# AD5764-AD7734_Synchronized.net
KiCad netlist of a schematic drawn in EAGLE
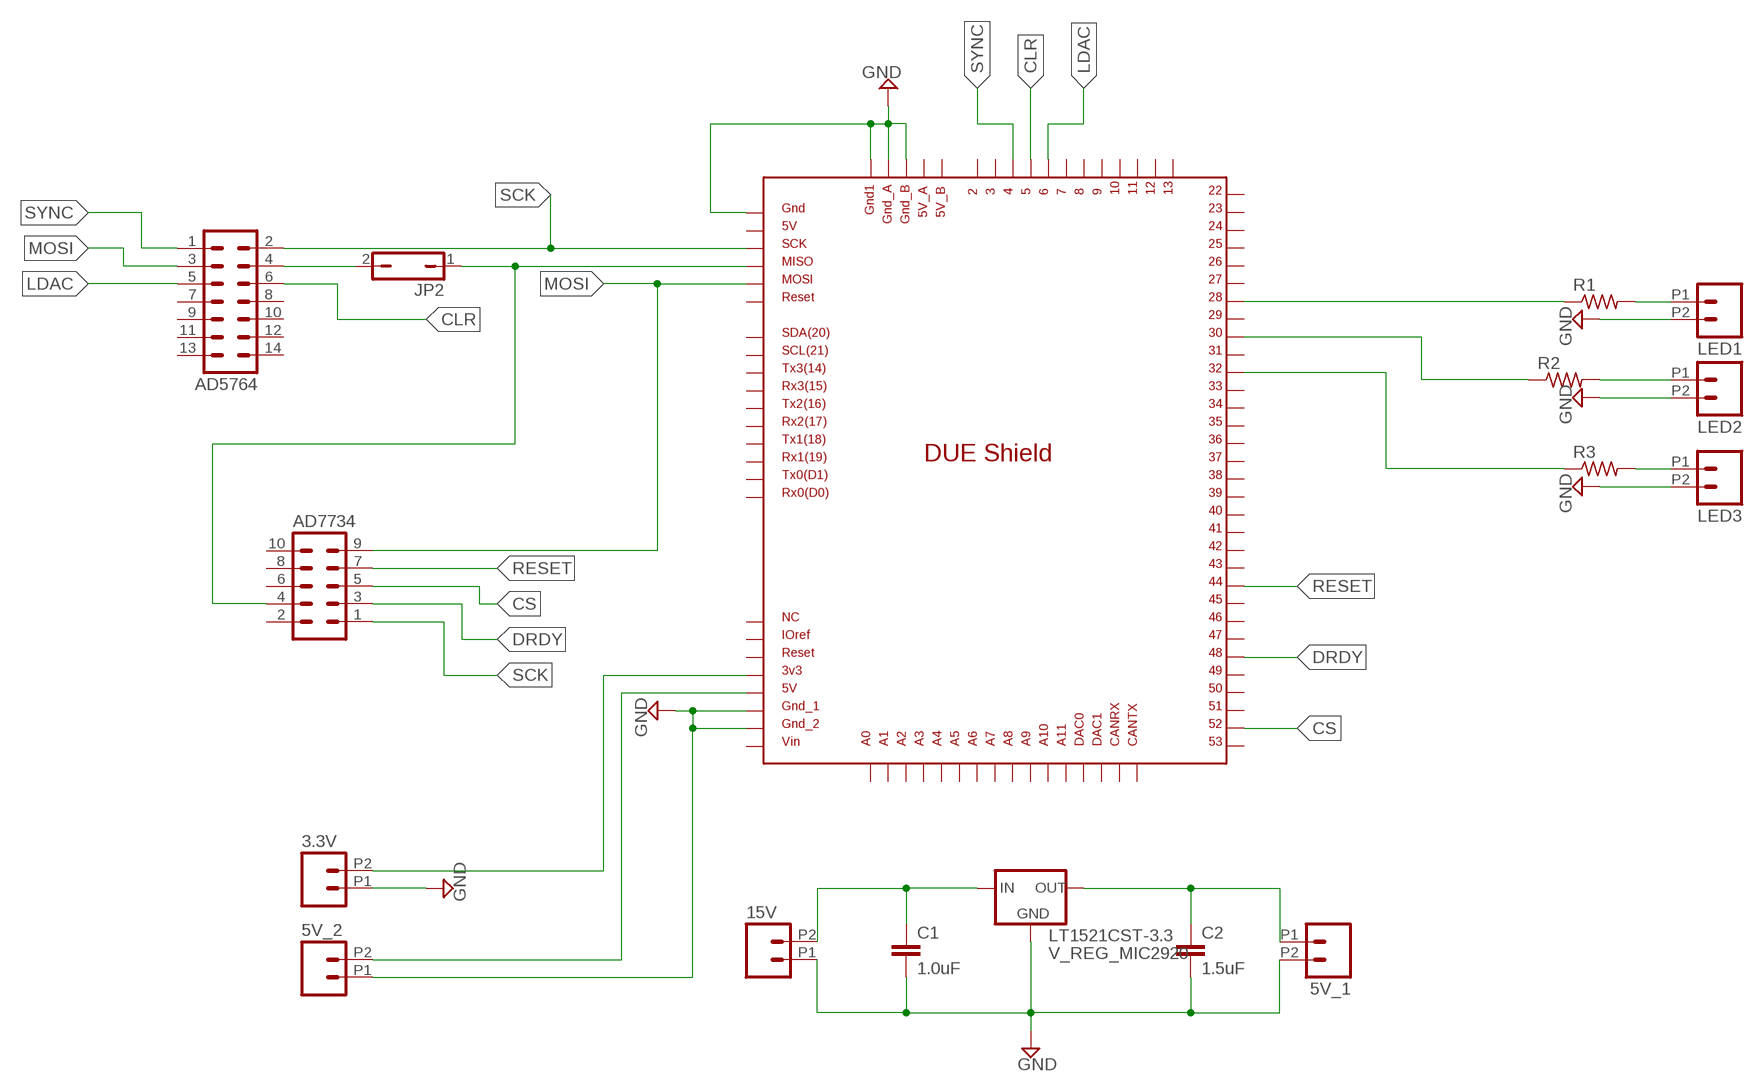
[diagram p0: schematic, sheet 1]

(export (version "E")
  (design (tool "Eeschema 10.0.6"))
  (components
    (comp (ref "3.3V")
      (value "M022.54MM_SCREWTERM")
      (footprint "eagle-import:1X02_2.54_SCREWTERM")
      (libsource (lib "eagle-import") (part "M022.54MM_SCREWTERM"))
    )
    (comp (ref "5V_1")
      (value "M022.54MM_SCREWTERM")
      (footprint "eagle-import:1X02_2.54_SCREWTERM")
      (libsource (lib "eagle-import") (part "M022.54MM_SCREWTERM"))
    )
    (comp (ref "5V_2")
      (value "M022.54MM_SCREWTERM")
      (footprint "eagle-import:1X02_2.54_SCREWTERM")
      (libsource (lib "eagle-import") (part "M022.54MM_SCREWTERM"))
    )
    (comp (ref "15V")
      (value "M022.54MM_SCREWTERM")
      (footprint "eagle-import:1X02_2.54_SCREWTERM")
      (libsource (lib "eagle-import") (part "M022.54MM_SCREWTERM"))
    )
    (comp (ref "AD5764")
      (value "MA07-2")
      (footprint "eagle-import:MA07-2")
      (libsource (lib "eagle-import") (part "MA07-2"))
    )
    (comp (ref "AD7734")
      (value "MA05-2")
      (footprint "eagle-import:MA05-2")
      (libsource (lib "eagle-import") (part "MA05-2"))
    )
    (comp (ref "C1")
      (value "1.0uF")
      (footprint "eagle-import:0603-CAP")
      (libsource (lib "eagle-import") (part "1.0UF-16V-10%(0603)"))
    )
    (comp (ref "C2")
      (value "1.5uF")
      (footprint "eagle-import:0603-CAP")
      (libsource (lib "eagle-import") (part "1.0UF-16V-10%(0603)"))
    )
    (comp (ref "JP2")
      (value "JP1Q")
      (footprint "eagle-import:JP1")
      (libsource (lib "eagle-import") (part "JP1Q"))
    )
    (comp (ref "LED1")
      (value "M022.54MM_SCREWTERM")
      (footprint "eagle-import:1X02_2.54_SCREWTERM")
      (libsource (lib "eagle-import") (part "M022.54MM_SCREWTERM"))
    )
    (comp (ref "LED2")
      (value "M022.54MM_SCREWTERM")
      (footprint "eagle-import:1X02_2.54_SCREWTERM")
      (libsource (lib "eagle-import") (part "M022.54MM_SCREWTERM"))
    )
    (comp (ref "LED3")
      (value "M022.54MM_SCREWTERM")
      (footprint "eagle-import:1X02_2.54_SCREWTERM")
      (libsource (lib "eagle-import") (part "M022.54MM_SCREWTERM"))
    )
    (comp (ref "LT1521CST-3.3")
      (value "V_REG_MIC2920")
      (footprint "eagle-import:SOT223")
      (libsource (lib "eagle-import") (part "V_REG_MIC2920"))
    )
    (comp (ref "R1")
      (value "R-US_R1206")
      (footprint "eagle-import:R1206")
      (libsource (lib "eagle-import") (part "R-US_R1206"))
    )
    (comp (ref "R2")
      (value "R-US_R1206")
      (footprint "eagle-import:R1206")
      (libsource (lib "eagle-import") (part "R-US_R1206"))
    )
    (comp (ref "R3")
      (value "R-US_R1206")
      (footprint "eagle-import:R1206")
      (libsource (lib "eagle-import") (part "R-US_R1206"))
    )
    (comp (ref "U$2")
      (value "DUE(REDUCED)")
      (footprint "eagle-import:DUE(REDUCED)")
      (libsource (lib "eagle-import") (part "DUE(REDUCED)"))
    )
  )
  (nets
    (net (code "1") (name "CLR") (class "Default")
      (node (ref "AD5764") (pin "6") (pinfunction "6_6") (pintype "passive"))
      (node (ref "U$2") (pin "5") (pinfunction "5_5") (pintype "bidirectional"))
    )
    (net (code "2") (name "CS") (class "Default")
      (node (ref "AD7734") (pin "5") (pinfunction "5_5") (pintype "passive"))
      (node (ref "U$2") (pin "52") (pinfunction "52_52") (pintype "bidirectional"))
    )
    (net (code "3") (name "DRDY") (class "Default")
      (node (ref "AD7734") (pin "3") (pinfunction "3_3") (pintype "passive"))
      (node (ref "U$2") (pin "48") (pinfunction "48_48") (pintype "bidirectional"))
    )
    (net (code "4") (name "GND") (class "Default")
      (node (ref "15V") (pin "P1") (pinfunction "1_P1") (pintype "passive"))
      (node (ref "3.3V") (pin "P1") (pinfunction "1_P1") (pintype "passive"))
      (node (ref "5V_1") (pin "P2") (pinfunction "2_P2") (pintype "passive"))
      (node (ref "5V_2") (pin "P1") (pinfunction "1_P1") (pintype "passive"))
      (node (ref "C1") (pin "2") (pinfunction "2_2") (pintype "passive"))
      (node (ref "C2") (pin "2") (pinfunction "2_2") (pintype "passive"))
      (node (ref "LED1") (pin "P2") (pinfunction "2_P2") (pintype "passive"))
      (node (ref "LED2") (pin "P2") (pinfunction "2_P2") (pintype "passive"))
      (node (ref "LED3") (pin "P2") (pinfunction "2_P2") (pintype "passive"))
      (node (ref "LT1521CST-3.3") (pin "2") (pinfunction "GND_2") (pintype "input"))
      (node (ref "U$2") (pin "5V_ICSP") (pinfunction "5V_ICSP_5V_ICSP") (pintype "bidirectional"))
      (node (ref "U$2") (pin "GND1") (pinfunction "GND1_GND1") (pintype "bidirectional"))
      (node (ref "U$2") (pin "GND_1") (pinfunction "GND_1_GND_1") (pintype "bidirectional"))
      (node (ref "U$2") (pin "GND_2") (pinfunction "GND_2_GND_2") (pintype "bidirectional"))
      (node (ref "U$2") (pin "GND_A") (pinfunction "GND_A_GND_A") (pintype "bidirectional"))
      (node (ref "U$2") (pin "GND_B") (pinfunction "GND_B_GND_B") (pintype "bidirectional"))
    )
    (net (code "5") (name "LDAC") (class "Default")
      (node (ref "AD5764") (pin "5") (pinfunction "5_5") (pintype "passive"))
      (node (ref "U$2") (pin "6") (pinfunction "6_6") (pintype "bidirectional"))
    )
    (net (code "6") (name "MOSI") (class "Default")
      (node (ref "AD5764") (pin "3") (pinfunction "3_3") (pintype "passive"))
      (node (ref "AD7734") (pin "9") (pinfunction "9_9") (pintype "passive"))
      (node (ref "U$2") (pin "MOSI_ICSP") (pinfunction "MOSI_ICSP_MOSI_ICSP") (pintype "bidirectional"))
    )
    (net (code "7") (name "Net-(3.3V-2)") (class "Default")
      (node (ref "3.3V") (pin "P2") (pinfunction "2_P2") (pintype "passive"))
      (node (ref "U$2") (pin "3V3") (pinfunction "3V3_3V3") (pintype "bidirectional"))
    )
    (net (code "8") (name "Net-(5V_1-1)") (class "Default")
      (node (ref "5V_1") (pin "P1") (pinfunction "1_P1") (pintype "passive"))
      (node (ref "C2") (pin "1") (pinfunction "1_1") (pintype "passive"))
      (node (ref "LT1521CST-3.3") (pin "3") (pinfunction "OUT_3") (pintype "passive"))
    )
    (net (code "9") (name "Net-(5V_2-2)") (class "Default")
      (node (ref "5V_2") (pin "P2") (pinfunction "2_P2") (pintype "passive"))
      (node (ref "U$2") (pin "5V") (pinfunction "5V_5V") (pintype "bidirectional"))
    )
    (net (code "10") (name "Net-(15V-2)") (class "Default")
      (node (ref "15V") (pin "P2") (pinfunction "2_P2") (pintype "passive"))
      (node (ref "C1") (pin "1") (pinfunction "1_1") (pintype "passive"))
      (node (ref "LT1521CST-3.3") (pin "1") (pinfunction "IN_1") (pintype "input"))
    )
    (net (code "11") (name "Net-(AD5764-Pad4)") (class "Default")
      (node (ref "AD5764") (pin "4") (pinfunction "4_4") (pintype "passive"))
      (node (ref "JP2") (pin "2") (pinfunction "2_2") (pintype "passive"))
    )
    (net (code "12") (name "Net-(AD7734-Pad4)") (class "Default")
      (node (ref "AD7734") (pin "4") (pinfunction "4_4") (pintype "passive"))
      (node (ref "JP2") (pin "1") (pinfunction "1_1") (pintype "passive"))
      (node (ref "U$2") (pin "MISO_ICSP") (pinfunction "MISO_ICSP_MISO_ICSP") (pintype "bidirectional"))
    )
    (net (code "13") (name "Net-(LED1-1)") (class "Default")
      (node (ref "LED1") (pin "P1") (pinfunction "1_P1") (pintype "passive"))
      (node (ref "R1") (pin "2") (pinfunction "2_2") (pintype "passive"))
    )
    (net (code "14") (name "Net-(LED2-1)") (class "Default")
      (node (ref "LED2") (pin "P1") (pinfunction "1_P1") (pintype "passive"))
      (node (ref "R2") (pin "2") (pinfunction "2_2") (pintype "passive"))
    )
    (net (code "15") (name "Net-(LED3-1)") (class "Default")
      (node (ref "LED3") (pin "P1") (pinfunction "1_P1") (pintype "passive"))
      (node (ref "R3") (pin "2") (pinfunction "2_2") (pintype "passive"))
    )
    (net (code "16") (name "Net-(R1-Pad1)") (class "Default")
      (node (ref "R1") (pin "1") (pinfunction "1_1") (pintype "passive"))
      (node (ref "U$2") (pin "28") (pinfunction "28_28") (pintype "bidirectional"))
    )
    (net (code "17") (name "Net-(R2-Pad1)") (class "Default")
      (node (ref "R2") (pin "1") (pinfunction "1_1") (pintype "passive"))
      (node (ref "U$2") (pin "30") (pinfunction "30_30") (pintype "bidirectional"))
    )
    (net (code "18") (name "Net-(R3-Pad1)") (class "Default")
      (node (ref "R3") (pin "1") (pinfunction "1_1") (pintype "passive"))
      (node (ref "U$2") (pin "32") (pinfunction "32_32") (pintype "bidirectional"))
    )
    (net (code "19") (name "RESET") (class "Default")
      (node (ref "AD7734") (pin "7") (pinfunction "7_7") (pintype "passive"))
      (node (ref "U$2") (pin "44") (pinfunction "44_44") (pintype "bidirectional"))
    )
    (net (code "20") (name "SCK") (class "Default")
      (node (ref "AD5764") (pin "2") (pinfunction "2_2") (pintype "passive"))
      (node (ref "AD7734") (pin "1") (pinfunction "1_1") (pintype "passive"))
      (node (ref "U$2") (pin "SCK_ICSP") (pinfunction "SCK_ICSP_SCK_ICSP") (pintype "bidirectional"))
    )
    (net (code "21") (name "SYNC") (class "Default")
      (node (ref "AD5764") (pin "1") (pinfunction "1_1") (pintype "passive"))
      (node (ref "U$2") (pin "4") (pinfunction "4_4") (pintype "bidirectional"))
    )
    (net (code "22") (name "unconnected-(AD5764-Pad7)") (class "Default")
      (node (ref "AD5764") (pin "7") (pinfunction "7_7") (pintype "passive"))
    )
    (net (code "23") (name "unconnected-(AD5764-Pad8)") (class "Default")
      (node (ref "AD5764") (pin "8") (pinfunction "8_8") (pintype "passive"))
    )
    (net (code "24") (name "unconnected-(AD5764-Pad9)") (class "Default")
      (node (ref "AD5764") (pin "9") (pinfunction "9_9") (pintype "passive"))
    )
    (net (code "25") (name "unconnected-(AD5764-Pad10)") (class "Default")
      (node (ref "AD5764") (pin "10") (pinfunction "10_10") (pintype "passive"))
    )
    (net (code "26") (name "unconnected-(AD5764-Pad11)") (class "Default")
      (node (ref "AD5764") (pin "11") (pinfunction "11_11") (pintype "passive"))
    )
    (net (code "27") (name "unconnected-(AD5764-Pad12)") (class "Default")
      (node (ref "AD5764") (pin "12") (pinfunction "12_12") (pintype "passive"))
    )
    (net (code "28") (name "unconnected-(AD5764-Pad13)") (class "Default")
      (node (ref "AD5764") (pin "13") (pinfunction "13_13") (pintype "passive"))
    )
    (net (code "29") (name "unconnected-(AD5764-Pad14)") (class "Default")
      (node (ref "AD5764") (pin "14") (pinfunction "14_14") (pintype "passive"))
    )
    (net (code "30") (name "unconnected-(AD7734-Pad2)") (class "Default")
      (node (ref "AD7734") (pin "2") (pinfunction "2_2") (pintype "passive"))
    )
    (net (code "31") (name "unconnected-(AD7734-Pad6)") (class "Default")
      (node (ref "AD7734") (pin "6") (pinfunction "6_6") (pintype "passive"))
    )
    (net (code "32") (name "unconnected-(AD7734-Pad8)") (class "Default")
      (node (ref "AD7734") (pin "8") (pinfunction "8_8") (pintype "passive"))
    )
    (net (code "33") (name "unconnected-(AD7734-Pad10)") (class "Default")
      (node (ref "AD7734") (pin "10") (pinfunction "10_10") (pintype "passive"))
    )
    (net (code "34") (name "unconnected-(U$2-Pad2)") (class "Default")
      (node (ref "U$2") (pin "2") (pinfunction "2_2") (pintype "bidirectional"))
    )
    (net (code "35") (name "unconnected-(U$2-Pad3)") (class "Default")
      (node (ref "U$2") (pin "3") (pinfunction "3_3") (pintype "bidirectional"))
    )
    (net (code "36") (name "unconnected-(U$2-Pad5V_A)") (class "Default")
      (node (ref "U$2") (pin "5V_A") (pinfunction "5V_A_5V_A") (pintype "bidirectional"))
    )
    (net (code "37") (name "unconnected-(U$2-Pad5V_B)") (class "Default")
      (node (ref "U$2") (pin "5V_B") (pinfunction "5V_B_5V_B") (pintype "bidirectional"))
    )
    (net (code "38") (name "unconnected-(U$2-Pad7)") (class "Default")
      (node (ref "U$2") (pin "7") (pinfunction "7_7") (pintype "bidirectional"))
    )
    (net (code "39") (name "unconnected-(U$2-Pad8)") (class "Default")
      (node (ref "U$2") (pin "8") (pinfunction "8_8") (pintype "bidirectional"))
    )
    (net (code "40") (name "unconnected-(U$2-Pad9)") (class "Default")
      (node (ref "U$2") (pin "9") (pinfunction "9_9") (pintype "bidirectional"))
    )
    (net (code "41") (name "unconnected-(U$2-Pad10)") (class "Default")
      (node (ref "U$2") (pin "10") (pinfunction "10_10") (pintype "bidirectional"))
    )
    (net (code "42") (name "unconnected-(U$2-Pad11)") (class "Default")
      (node (ref "U$2") (pin "11") (pinfunction "11_11") (pintype "bidirectional"))
    )
    (net (code "43") (name "unconnected-(U$2-Pad12)") (class "Default")
      (node (ref "U$2") (pin "12") (pinfunction "12_12") (pintype "bidirectional"))
    )
    (net (code "44") (name "unconnected-(U$2-Pad13)") (class "Default")
      (node (ref "U$2") (pin "13") (pinfunction "13_13") (pintype "bidirectional"))
    )
    (net (code "45") (name "unconnected-(U$2-Pad22)") (class "Default")
      (node (ref "U$2") (pin "22") (pinfunction "22_22") (pintype "bidirectional"))
    )
    (net (code "46") (name "unconnected-(U$2-Pad23)") (class "Default")
      (node (ref "U$2") (pin "23") (pinfunction "23_23") (pintype "bidirectional"))
    )
    (net (code "47") (name "unconnected-(U$2-Pad24)") (class "Default")
      (node (ref "U$2") (pin "24") (pinfunction "24_24") (pintype "bidirectional"))
    )
    (net (code "48") (name "unconnected-(U$2-Pad25)") (class "Default")
      (node (ref "U$2") (pin "25") (pinfunction "25_25") (pintype "bidirectional"))
    )
    (net (code "49") (name "unconnected-(U$2-Pad26)") (class "Default")
      (node (ref "U$2") (pin "26") (pinfunction "26_26") (pintype "bidirectional"))
    )
    (net (code "50") (name "unconnected-(U$2-Pad27)") (class "Default")
      (node (ref "U$2") (pin "27") (pinfunction "27_27") (pintype "bidirectional"))
    )
    (net (code "51") (name "unconnected-(U$2-Pad29)") (class "Default")
      (node (ref "U$2") (pin "29") (pinfunction "29_29") (pintype "bidirectional"))
    )
    (net (code "52") (name "unconnected-(U$2-Pad31)") (class "Default")
      (node (ref "U$2") (pin "31") (pinfunction "31_31") (pintype "bidirectional"))
    )
    (net (code "53") (name "unconnected-(U$2-Pad33)") (class "Default")
      (node (ref "U$2") (pin "33") (pinfunction "33_33") (pintype "bidirectional"))
    )
    (net (code "54") (name "unconnected-(U$2-Pad34)") (class "Default")
      (node (ref "U$2") (pin "34") (pinfunction "34_34") (pintype "bidirectional"))
    )
    (net (code "55") (name "unconnected-(U$2-Pad35)") (class "Default")
      (node (ref "U$2") (pin "35") (pinfunction "35_35") (pintype "bidirectional"))
    )
    (net (code "56") (name "unconnected-(U$2-Pad36)") (class "Default")
      (node (ref "U$2") (pin "36") (pinfunction "36_36") (pintype "bidirectional"))
    )
    (net (code "57") (name "unconnected-(U$2-Pad37)") (class "Default")
      (node (ref "U$2") (pin "37") (pinfunction "37_37") (pintype "bidirectional"))
    )
    (net (code "58") (name "unconnected-(U$2-Pad38)") (class "Default")
      (node (ref "U$2") (pin "38") (pinfunction "38_38") (pintype "bidirectional"))
    )
    (net (code "59") (name "unconnected-(U$2-Pad39)") (class "Default")
      (node (ref "U$2") (pin "39") (pinfunction "39_39") (pintype "bidirectional"))
    )
    (net (code "60") (name "unconnected-(U$2-Pad40)") (class "Default")
      (node (ref "U$2") (pin "40") (pinfunction "40_40") (pintype "bidirectional"))
    )
    (net (code "61") (name "unconnected-(U$2-Pad41)") (class "Default")
      (node (ref "U$2") (pin "41") (pinfunction "41_41") (pintype "bidirectional"))
    )
    (net (code "62") (name "unconnected-(U$2-Pad42)") (class "Default")
      (node (ref "U$2") (pin "42") (pinfunction "42_42") (pintype "bidirectional"))
    )
    (net (code "63") (name "unconnected-(U$2-Pad43)") (class "Default")
      (node (ref "U$2") (pin "43") (pinfunction "43_43") (pintype "bidirectional"))
    )
    (net (code "64") (name "unconnected-(U$2-Pad45)") (class "Default")
      (node (ref "U$2") (pin "45") (pinfunction "45_45") (pintype "bidirectional"))
    )
    (net (code "65") (name "unconnected-(U$2-Pad46)") (class "Default")
      (node (ref "U$2") (pin "46") (pinfunction "46_46") (pintype "bidirectional"))
    )
    (net (code "66") (name "unconnected-(U$2-Pad47)") (class "Default")
      (node (ref "U$2") (pin "47") (pinfunction "47_47") (pintype "bidirectional"))
    )
    (net (code "67") (name "unconnected-(U$2-Pad49)") (class "Default")
      (node (ref "U$2") (pin "49") (pinfunction "49_49") (pintype "bidirectional"))
    )
    (net (code "68") (name "unconnected-(U$2-Pad50)") (class "Default")
      (node (ref "U$2") (pin "50") (pinfunction "50_50") (pintype "bidirectional"))
    )
    (net (code "69") (name "unconnected-(U$2-Pad51)") (class "Default")
      (node (ref "U$2") (pin "51") (pinfunction "51_51") (pintype "bidirectional"))
    )
    (net (code "70") (name "unconnected-(U$2-Pad53)") (class "Default")
      (node (ref "U$2") (pin "53") (pinfunction "53_53") (pintype "bidirectional"))
    )
    (net (code "71") (name "unconnected-(U$2-PadA0)") (class "Default")
      (node (ref "U$2") (pin "A0") (pinfunction "A0_A0") (pintype "bidirectional"))
    )
    (net (code "72") (name "unconnected-(U$2-PadA1)") (class "Default")
      (node (ref "U$2") (pin "A1") (pinfunction "A1_A1") (pintype "bidirectional"))
    )
    (net (code "73") (name "unconnected-(U$2-PadA2)") (class "Default")
      (node (ref "U$2") (pin "A2") (pinfunction "A2_A2") (pintype "bidirectional"))
    )
    (net (code "74") (name "unconnected-(U$2-PadA3)") (class "Default")
      (node (ref "U$2") (pin "A3") (pinfunction "A3_A3") (pintype "bidirectional"))
    )
    (net (code "75") (name "unconnected-(U$2-PadA4)") (class "Default")
      (node (ref "U$2") (pin "A4") (pinfunction "A4_A4") (pintype "bidirectional"))
    )
    (net (code "76") (name "unconnected-(U$2-PadA5)") (class "Default")
      (node (ref "U$2") (pin "A5") (pinfunction "A5_A5") (pintype "bidirectional"))
    )
    (net (code "77") (name "unconnected-(U$2-PadA6)") (class "Default")
      (node (ref "U$2") (pin "A6") (pinfunction "A6_A6") (pintype "bidirectional"))
    )
    (net (code "78") (name "unconnected-(U$2-PadA7)") (class "Default")
      (node (ref "U$2") (pin "A7") (pinfunction "A7_A7") (pintype "bidirectional"))
    )
    (net (code "79") (name "unconnected-(U$2-PadA8)") (class "Default")
      (node (ref "U$2") (pin "A8") (pinfunction "A8_A8") (pintype "bidirectional"))
    )
    (net (code "80") (name "unconnected-(U$2-PadA9)") (class "Default")
      (node (ref "U$2") (pin "A9") (pinfunction "A9_A9") (pintype "bidirectional"))
    )
    (net (code "81") (name "unconnected-(U$2-PadA10)") (class "Default")
      (node (ref "U$2") (pin "A10") (pinfunction "A10_A10") (pintype "bidirectional"))
    )
    (net (code "82") (name "unconnected-(U$2-PadA11)") (class "Default")
      (node (ref "U$2") (pin "A11") (pinfunction "A11_A11") (pintype "bidirectional"))
    )
    (net (code "83") (name "unconnected-(U$2-PadCANRX)") (class "Default")
      (node (ref "U$2") (pin "CANRX") (pinfunction "CANRX_CANRX") (pintype "bidirectional"))
    )
    (net (code "84") (name "unconnected-(U$2-PadCANTX)") (class "Default")
      (node (ref "U$2") (pin "CANTX") (pinfunction "CANTX_CANTX") (pintype "bidirectional"))
    )
    (net (code "85") (name "unconnected-(U$2-PadDAC0)") (class "Default")
      (node (ref "U$2") (pin "DAC0") (pinfunction "DAC0_DAC0") (pintype "bidirectional"))
    )
    (net (code "86") (name "unconnected-(U$2-PadDAC1)") (class "Default")
      (node (ref "U$2") (pin "DAC1") (pinfunction "DAC1_DAC1") (pintype "bidirectional"))
    )
    (net (code "87") (name "unconnected-(U$2-PadGND_ICSP)") (class "Default")
      (node (ref "U$2") (pin "GND_ICSP") (pinfunction "GND_ICSP_GND_ICSP") (pintype "bidirectional"))
    )
    (net (code "88") (name "unconnected-(U$2-PadIOREF)") (class "Default")
      (node (ref "U$2") (pin "IOREF") (pinfunction "IOREF_IOREF") (pintype "bidirectional"))
    )
    (net (code "89") (name "unconnected-(U$2-PadNC)") (class "Default")
      (node (ref "U$2") (pin "NC") (pinfunction "NC_NC") (pintype "bidirectional"))
    )
    (net (code "90") (name "unconnected-(U$2-PadRESET)") (class "Default")
      (node (ref "U$2") (pin "RESET") (pinfunction "RESET_RESET") (pintype "bidirectional"))
    )
    (net (code "91") (name "unconnected-(U$2-PadRESET_ICSP)") (class "Default")
      (node (ref "U$2") (pin "RESET_ICSP") (pinfunction "RESET_ICSP_RESET_ICSP") (pintype "bidirectional"))
    )
    (net (code "92") (name "unconnected-(U$2-PadRX0)") (class "Default")
      (node (ref "U$2") (pin "RX0") (pinfunction "RX0_RX0") (pintype "bidirectional"))
    )
    (net (code "93") (name "unconnected-(U$2-PadRX1)") (class "Default")
      (node (ref "U$2") (pin "RX1") (pinfunction "RX1_RX1") (pintype "bidirectional"))
    )
    (net (code "94") (name "unconnected-(U$2-PadRX2)") (class "Default")
      (node (ref "U$2") (pin "RX2") (pinfunction "RX2_RX2") (pintype "bidirectional"))
    )
    (net (code "95") (name "unconnected-(U$2-PadRX3)") (class "Default")
      (node (ref "U$2") (pin "RX3") (pinfunction "RX3_RX3") (pintype "bidirectional"))
    )
    (net (code "96") (name "unconnected-(U$2-PadSCL)") (class "Default")
      (node (ref "U$2") (pin "SCL") (pinfunction "SCL_SCL") (pintype "bidirectional"))
    )
    (net (code "97") (name "unconnected-(U$2-PadSDA)") (class "Default")
      (node (ref "U$2") (pin "SDA") (pinfunction "SDA_SDA") (pintype "bidirectional"))
    )
    (net (code "98") (name "unconnected-(U$2-PadTX0)") (class "Default")
      (node (ref "U$2") (pin "TX0") (pinfunction "TX0_TX0") (pintype "bidirectional"))
    )
    (net (code "99") (name "unconnected-(U$2-PadTX1)") (class "Default")
      (node (ref "U$2") (pin "TX1") (pinfunction "TX1_TX1") (pintype "bidirectional"))
    )
    (net (code "100") (name "unconnected-(U$2-PadTX2)") (class "Default")
      (node (ref "U$2") (pin "TX2") (pinfunction "TX2_TX2") (pintype "bidirectional"))
    )
    (net (code "101") (name "unconnected-(U$2-PadTX3)") (class "Default")
      (node (ref "U$2") (pin "TX3") (pinfunction "TX3_TX3") (pintype "bidirectional"))
    )
    (net (code "102") (name "unconnected-(U$2-PadVIN)") (class "Default")
      (node (ref "U$2") (pin "VIN") (pinfunction "VIN_VIN") (pintype "bidirectional"))
    )
  )
)
